# STM32_F4VE.net
KiCad netlist of a schematic drawn in Altium Designer
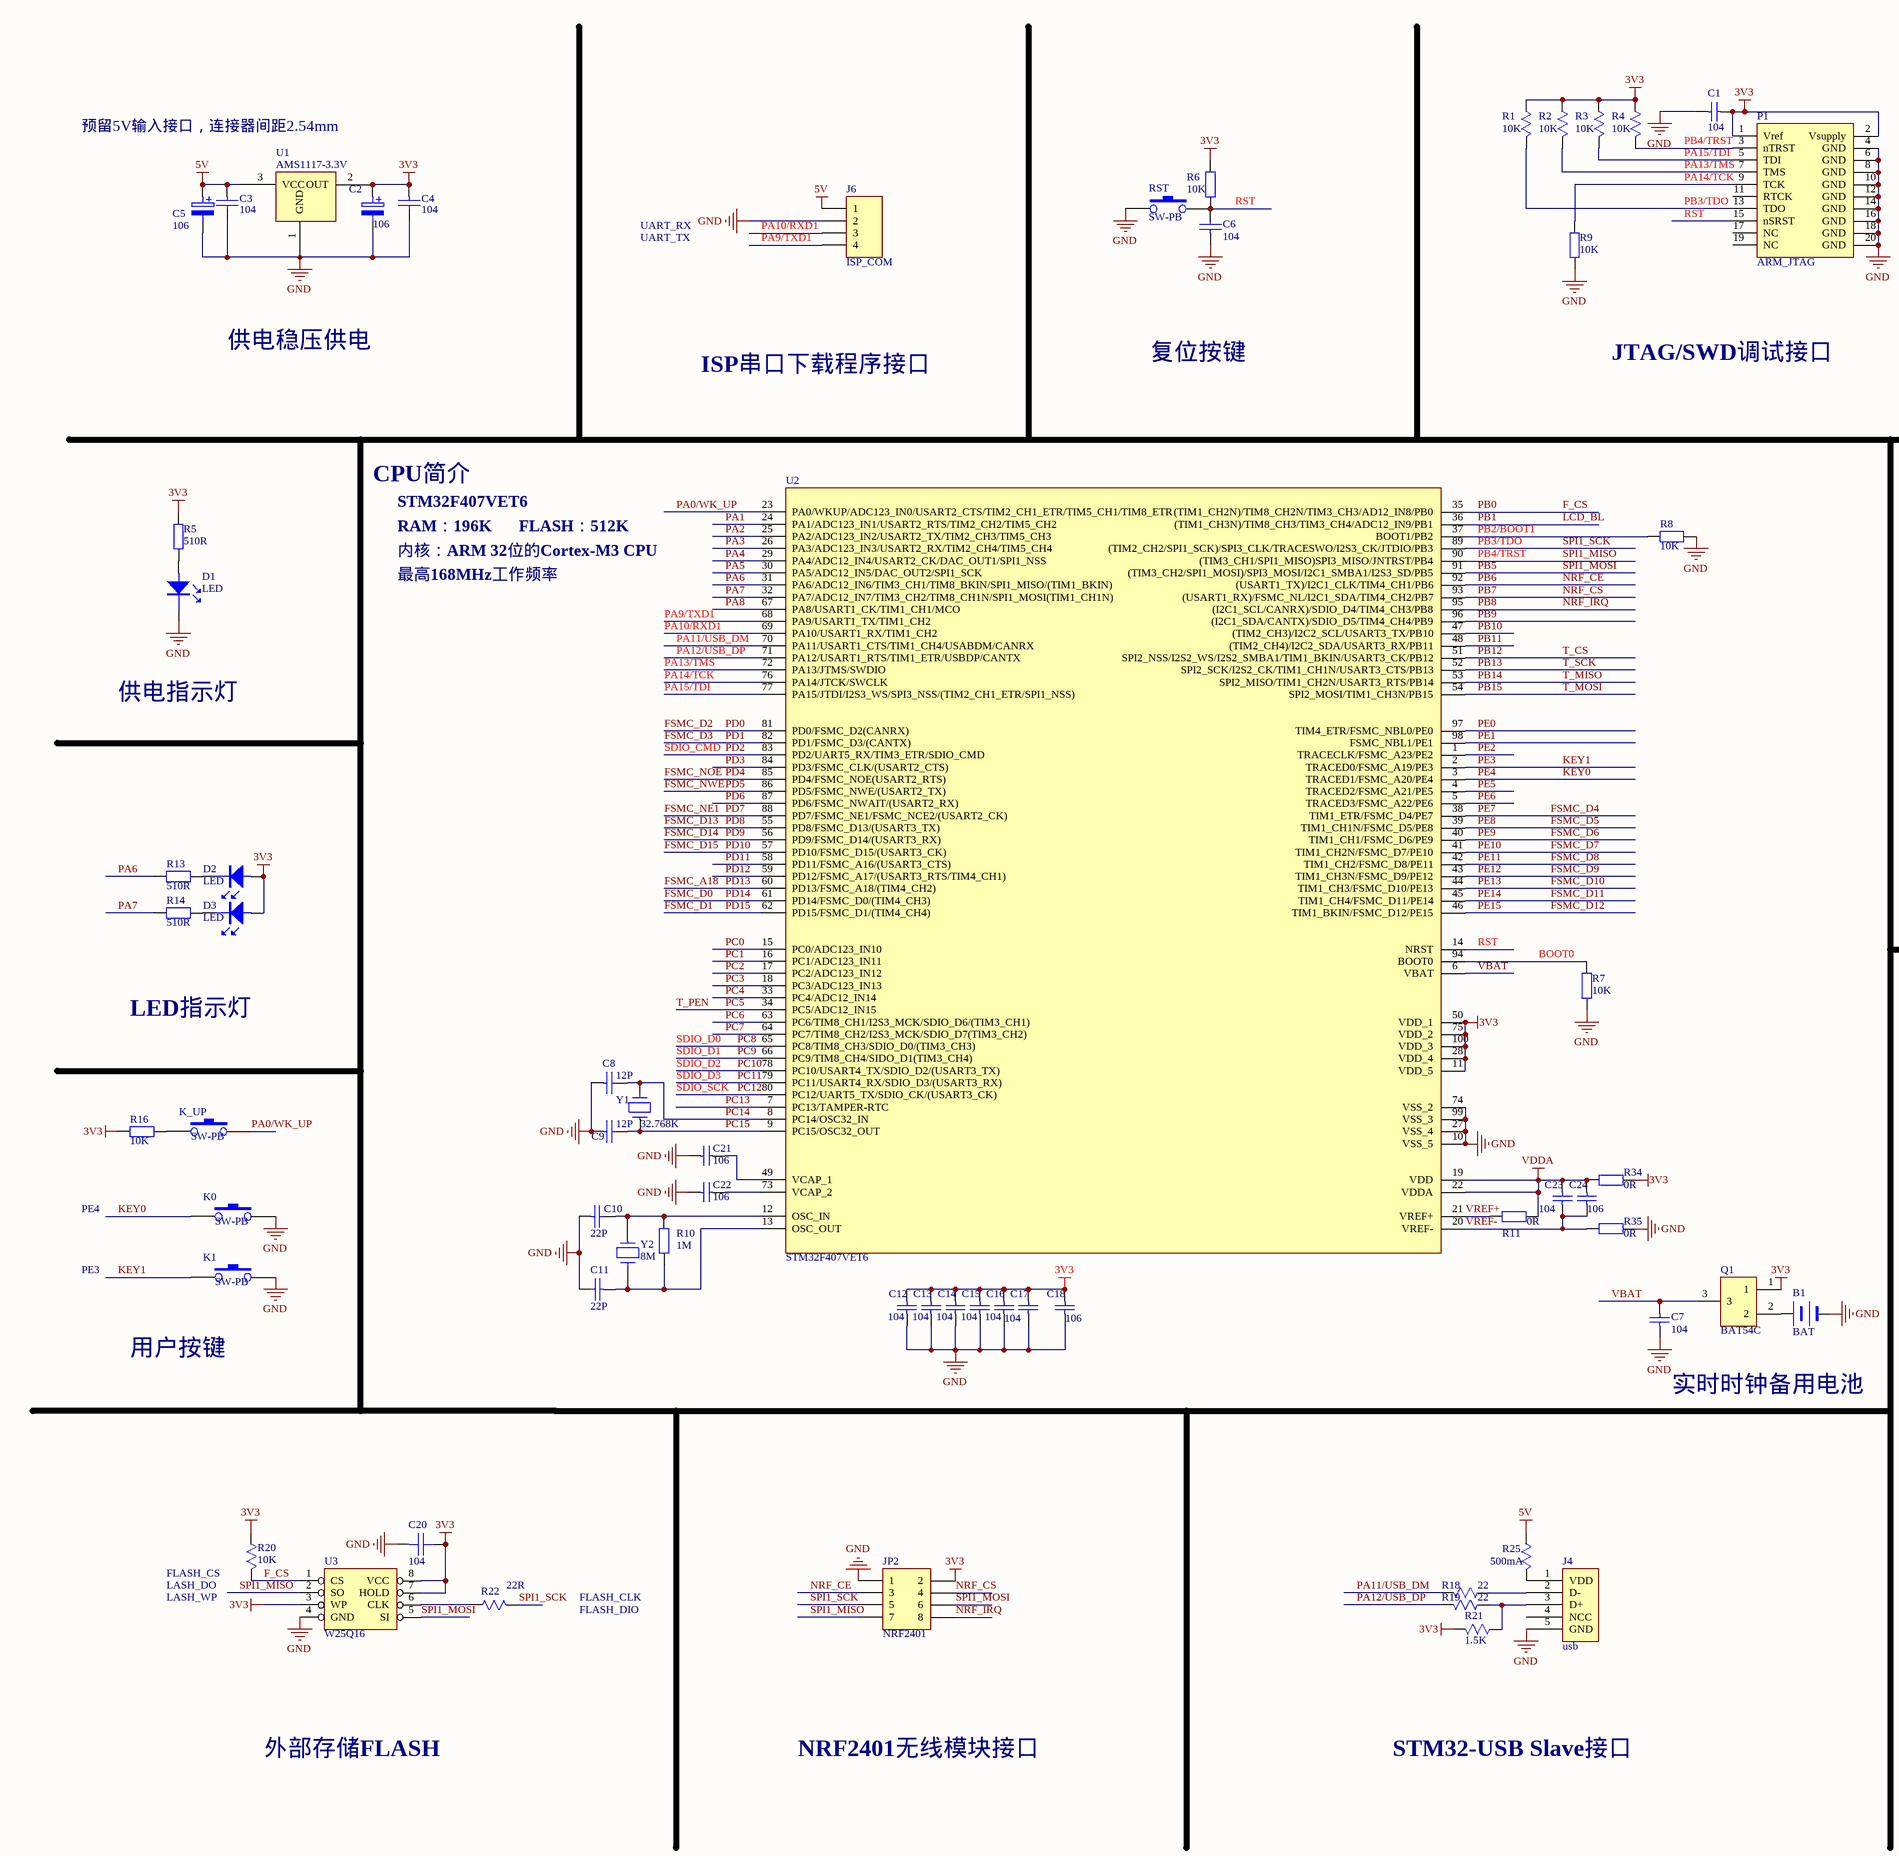
[diagram p0: STM32_F4VE.SchDoc, left]
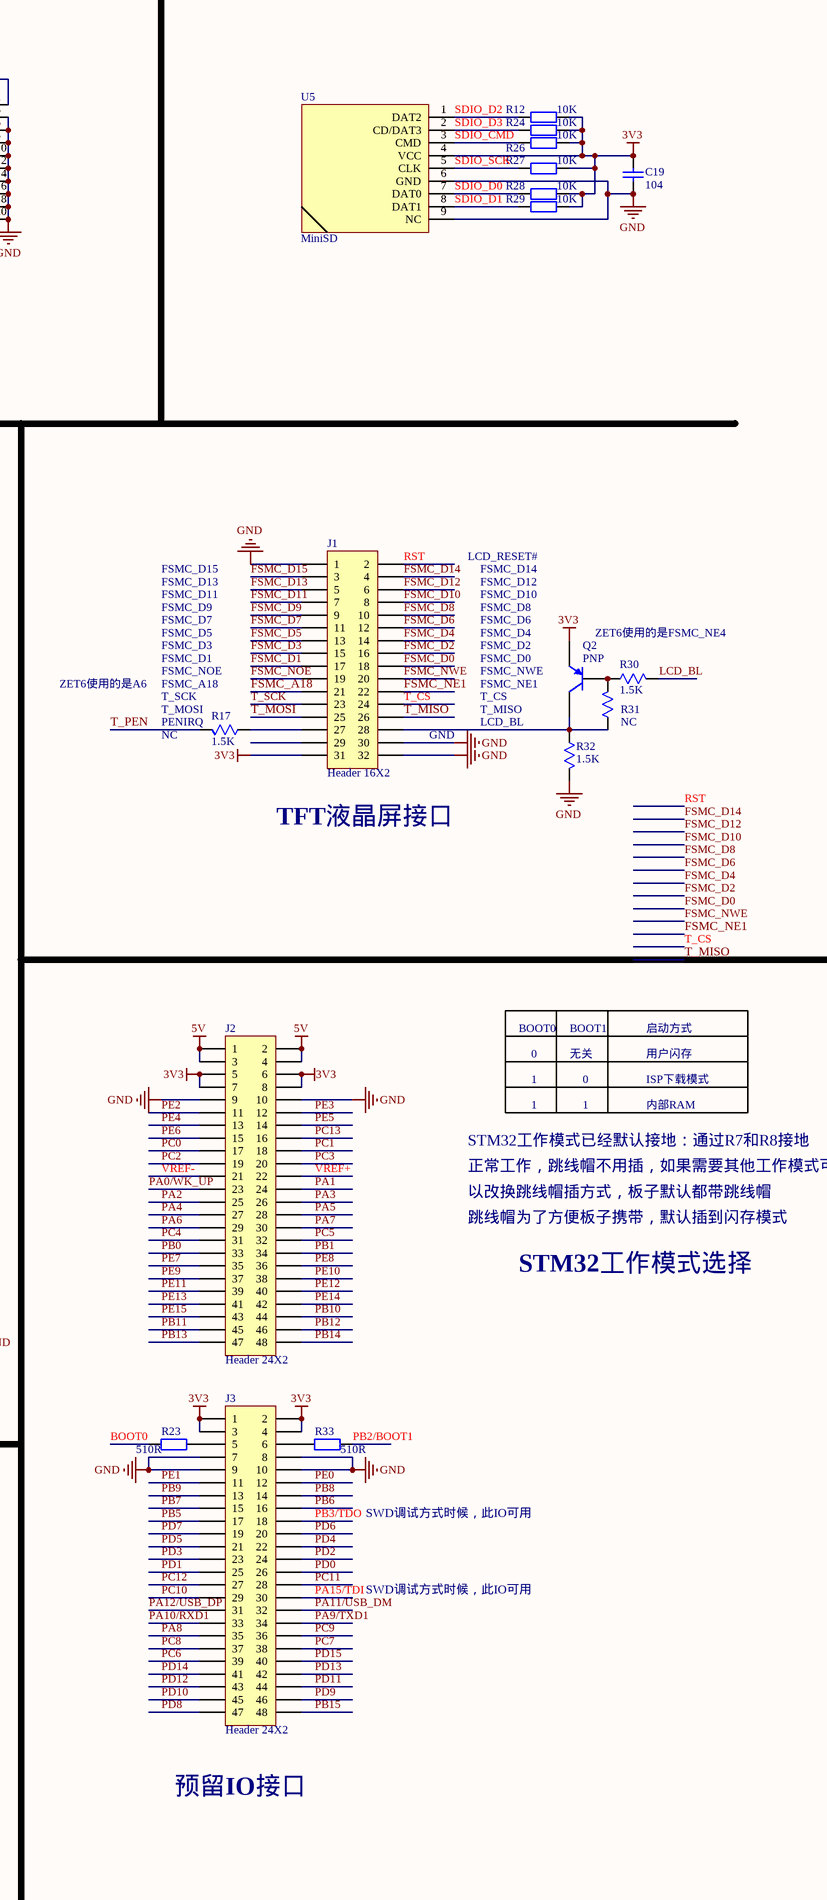
[diagram p1: STM32_F4VE.SchDoc, right]

(export (version "E")
  (design (tool "Eeschema 10.0.6"))
  (components
    (comp (ref "B1") (value "BAT") (footprint "BAT") (libsource (lib "*") (part "BATTERY")))
    (comp (ref "C1")
      (value "104")
      (footprint "RC0603")
      (description "Capacitor")
      (fields (field (name "PUBLISHER") "Altium Limited"))
      (libsource (lib "*") (part "Cap"))
    )
    (comp (ref "C2") (value "106") (footprint "RC0805") (libsource (lib "*") (part "ELECTRO2")))
    (comp (ref "C3")
      (value "104")
      (footprint "RC0603")
      (description "Capacitor")
      (libsource (lib "") (part "CAP_2"))
    )
    (comp (ref "C4")
      (value "104")
      (footprint "RC0603")
      (description "Capacitor")
      (libsource (lib "") (part "CAP_2"))
    )
    (comp (ref "C5") (value "106") (footprint "RC0805") (libsource (lib "*") (part "ELECTRO2")))
    (comp (ref "C6")
      (value "104")
      (footprint "RC0603")
      (description "Capacitor")
      (libsource (lib "*") (part "CAP"))
    )
    (comp (ref "C7")
      (value "104")
      (footprint "RC0603")
      (description "Capacitor")
      (fields (field (name "PUBLISHER") "Altium Limited"))
      (libsource (lib "") (part "Cap_1"))
    )
    (comp (ref "C8") (value "12P") (footprint "RC0603") (libsource (lib "") (part "CAP_1")))
    (comp (ref "C9") (value "12P") (footprint "RC0603") (libsource (lib "") (part "CAP_1")))
    (comp (ref "C10")
      (value "22P")
      (footprint "RC0603")
      (description "Capacitor")
      (libsource (lib "*") (part "CAP"))
    )
    (comp (ref "C11")
      (value "22P")
      (footprint "RC0603")
      (description "Capacitor")
      (libsource (lib "*") (part "CAP"))
    )
    (comp (ref "C12")
      (value "104")
      (footprint "RC0603")
      (description "Capacitor")
      (fields (field (name "PUBLISHER") "Altium Limited"))
      (libsource (lib "*") (part "Cap"))
    )
    (comp (ref "C13")
      (value "104")
      (footprint "RC0603")
      (description "Capacitor")
      (fields (field (name "PUBLISHER") "Altium Limited"))
      (libsource (lib "*") (part "Cap"))
    )
    (comp (ref "C14")
      (value "104")
      (footprint "RC0603")
      (description "Capacitor")
      (fields (field (name "PUBLISHER") "Altium Limited"))
      (libsource (lib "*") (part "Cap"))
    )
    (comp (ref "C15")
      (value "104")
      (footprint "RC0603")
      (description "Capacitor")
      (fields (field (name "PUBLISHER") "Altium Limited"))
      (libsource (lib "*") (part "Cap"))
    )
    (comp (ref "C16")
      (value "104")
      (footprint "RC0603")
      (description "Capacitor")
      (fields (field (name "PUBLISHER") "Altium Limited"))
      (libsource (lib "*") (part "Cap"))
    )
    (comp (ref "C17")
      (value "104")
      (footprint "RC0603")
      (description "Capacitor")
      (fields (field (name "PUBLISHER") "Altium Limited"))
      (libsource (lib "*") (part "Cap"))
    )
    (comp (ref "C18")
      (value "106")
      (footprint "RC0805")
      (description "Capacitor")
      (fields (field (name "PUBLISHER") "Altium Limited"))
      (libsource (lib "*") (part "Cap"))
    )
    (comp (ref "C19")
      (value "104")
      (footprint "RC0603")
      (description "Capacitor (Semiconductor SIM Model)")
      (fields (field (name "PUBLISHER") "Altium Limited"))
      (libsource (lib "*") (part "Cap Semi"))
    )
    (comp (ref "C20") (value "104") (footprint "RC0603") (libsource (lib "YT1_SCH_99SE") (part "CAP")))
    (comp (ref "C21")
      (value "106")
      (footprint "RC0805")
      (description "Capacitor")
      (fields (field (name "PUBLISHER") "Altium Limited"))
      (libsource (lib "*") (part "Cap"))
    )
    (comp (ref "C22")
      (value "106")
      (footprint "RC0805")
      (description "Capacitor")
      (fields (field (name "PUBLISHER") "Altium Limited"))
      (libsource (lib "*") (part "Cap"))
    )
    (comp (ref "C23")
      (value "104")
      (footprint "RC0603")
      (description "Capacitor")
      (fields (field (name "PUBLISHER") "Altium Limited"))
      (libsource (lib "*") (part "Cap"))
    )
    (comp (ref "C24")
      (value "106")
      (footprint "RC0805")
      (description "Capacitor")
      (fields (field (name "PUBLISHER") "Altium Limited"))
      (libsource (lib "*") (part "Cap"))
    )
    (comp (ref "D1") (value "LED") (footprint "LED0805") (libsource (lib "*") (part "LED")))
    (comp (ref "D2") (value "LED") (footprint "LED0805") (libsource (lib "*") (part "LED")))
    (comp (ref "D3") (value "LED") (footprint "LED0805") (libsource (lib "*") (part "LED")))
    (comp (ref "J1")
      (value "Header 16X2")
      (footprint "IDE2X16")
      (description "Header, 16-Pin, Dual row")
      (fields (field (name "PUBLISHER") "Altium Limited"))
      (libsource (lib "Miscellaneous Connectors") (part "Header 16X2"))
    )
    (comp (ref "J2")
      (value "Header 24X2")
      (footprint "IDE2X24")
      (description "Header, 24-Pin, Dual row")
      (fields (field (name "PUBLISHER") "Altium Limited"))
      (libsource (lib "Miscellaneous Connectors") (part "Header 24X2"))
    )
    (comp (ref "J3")
      (value "Header 24X2")
      (footprint "IDE2X24")
      (description "Header, 24-Pin, Dual row")
      (fields (field (name "PUBLISHER") "Altium Limited"))
      (libsource (lib "Miscellaneous Connectors") (part "Header 24X2"))
    )
    (comp (ref "J4") (value "usb") (footprint "Mini_USB") (libsource (lib "YT1_SCH_99SE") (part "usb")))
    (comp (ref "J6")
      (value "ISP_COM")
      (footprint "HDR1X4")
      (description "Header, 4-Pin")
      (fields (field (name "PUBLISHER") "Altium Limited"))
      (libsource (lib "Miscellaneous Connectors") (part "Header 4"))
    )
    (comp (ref "JP2")
      (value "NRF2401")
      (footprint "IDE2X4")
      (description "Header, 4-Pin, Dual row")
      (fields (field (name "PUBLISHER") "Altium Limited"))
      (libsource (lib "Miscellaneous Connectors") (part "Header 4X2"))
    )
    (comp (ref "K0") (value "SW-PB") (footprint "SW-SPST") (libsource (lib "*") (part "SW-PB")))
    (comp (ref "K1") (value "SW-PB") (footprint "SW-SPST") (libsource (lib "*") (part "SW-PB")))
    (comp (ref "K_UP") (value "SW-PB") (footprint "SW-SPST") (libsource (lib "*") (part "SW-PB")))
    (comp (ref "P1")
      (value "ARM_JTAG")
      (footprint "JTAG-20P")
      (description "JTAG")
      (libsource (lib "LXKJSJ") (part "JTAG"))
    )
    (comp (ref "Q1")
      (value "BAT54C")
      (footprint "SOT-23-BAT54C")
      (libsource (lib "Newcapec9263") (part "BAT54C"))
    )
    (comp (ref "Q2")
      (value "PNP")
      (footprint "PNP_SOT23")
      (description "PNP Bipolar Transistor")
      (fields (field (name "PUBLISHER") "Altium Limited"))
      (libsource (lib "Miscellaneous Devices") (part "PNP"))
    )
    (comp (ref "R1") (value "10K") (footprint "RC0603") (libsource (lib "YT1_SCH_99SE") (part "RES")))
    (comp (ref "R2") (value "10K") (footprint "RC0603") (libsource (lib "YT1_SCH_99SE") (part "RES")))
    (comp (ref "R3") (value "10K") (footprint "RC0603") (libsource (lib "YT1_SCH_99SE") (part "RES")))
    (comp (ref "R4") (value "10K") (footprint "RC0603") (libsource (lib "YT1_SCH_99SE") (part "RES")))
    (comp (ref "R5")
      (value "510R")
      (footprint "RC0603")
      (description "Resistor")
      (libsource (lib "") (part "Res2_3"))
    )
    (comp (ref "R6")
      (value "10K")
      (footprint "RC0603")
      (description "Resistor")
      (libsource (lib "") (part "Res2_1"))
    )
    (comp (ref "R7")
      (value "10K")
      (footprint "RC0603")
      (description "Resistor")
      (libsource (lib "") (part "Res2_3"))
    )
    (comp (ref "R8")
      (value "10K")
      (footprint "RC0603")
      (description "Resistor")
      (libsource (lib "") (part "Res2_2"))
    )
    (comp (ref "R9")
      (value "10K")
      (footprint "RC0603")
      (description "Resistor")
      (libsource (lib "") (part "Res2_3"))
    )
    (comp (ref "R10")
      (value "1M")
      (footprint "RC0603")
      (description "Resistor")
      (libsource (lib "") (part "Res2_1"))
    )
    (comp (ref "R11")
      (value "0R")
      (footprint "RC0603")
      (description "Resistor")
      (libsource (lib "Miscellaneous Devices") (part "Res2"))
    )
    (comp (ref "R12")
      (value "10K")
      (footprint "RC0603")
      (description "Resistor")
      (libsource (lib "Miscellaneous Devices") (part "Res2"))
    )
    (comp (ref "R13")
      (value "510R")
      (footprint "RC0603")
      (description "Resistor")
      (libsource (lib "Miscellaneous Devices") (part "Res2"))
    )
    (comp (ref "R14")
      (value "510R")
      (footprint "RC0603")
      (description "Resistor")
      (libsource (lib "Miscellaneous Devices") (part "Res2"))
    )
    (comp (ref "R16")
      (value "10K")
      (footprint "RC0603")
      (description "Resistor")
      (libsource (lib "") (part "Res2_2"))
    )
    (comp (ref "R17") (value "1.5K") (footprint "RC0603") (libsource (lib "YT1_SCH_99SE") (part "RES")))
    (comp (ref "R18") (value "22") (footprint "RC0603") (libsource (lib "YT1_SCH_99SE") (part "RES")))
    (comp (ref "R19") (value "22") (footprint "RC0603") (libsource (lib "YT1_SCH_99SE") (part "RES")))
    (comp (ref "R20") (value "10K") (footprint "RC0603") (libsource (lib "YT1_SCH_99SE") (part "RES")))
    (comp (ref "R21") (value "1.5K") (footprint "RC0603") (libsource (lib "YT1_SCH_99SE") (part "RES")))
    (comp (ref "R22") (value "22R") (footprint "RC0603") (libsource (lib "YT1_SCH_99SE") (part "RES")))
    (comp (ref "R23")
      (value "510R")
      (footprint "RC0603")
      (description "Resistor")
      (libsource (lib "Miscellaneous Devices") (part "Res2"))
    )
    (comp (ref "R24")
      (value "10K")
      (footprint "RC0603")
      (description "Resistor")
      (libsource (lib "Miscellaneous Devices") (part "Res2"))
    )
    (comp (ref "R25") (value "500mA") (footprint "RC0805") (libsource (lib "YT1_SCH_99SE") (part "RES")))
    (comp (ref "R26")
      (value "10K")
      (footprint "RC0603")
      (description "Resistor")
      (libsource (lib "Miscellaneous Devices") (part "Res2"))
    )
    (comp (ref "R27")
      (value "10K")
      (footprint "RC0603")
      (description "Resistor")
      (libsource (lib "Miscellaneous Devices") (part "Res2"))
    )
    (comp (ref "R28")
      (value "10K")
      (footprint "RC0603")
      (description "Resistor")
      (libsource (lib "Miscellaneous Devices") (part "Res2"))
    )
    (comp (ref "R29")
      (value "10K")
      (footprint "RC0603")
      (description "Resistor")
      (libsource (lib "Miscellaneous Devices") (part "Res2"))
    )
    (comp (ref "R30") (value "1.5K") (footprint "RC0603") (libsource (lib "YT1_SCH_99SE") (part "RES")))
    (comp (ref "R31") (value "NC") (footprint "RC0603") (libsource (lib "YT1_SCH_99SE") (part "RES")))
    (comp (ref "R32") (value "1.5K") (footprint "RC0603") (libsource (lib "YT1_SCH_99SE") (part "RES")))
    (comp (ref "R33")
      (value "510R")
      (footprint "RC0603")
      (description "Resistor")
      (libsource (lib "Miscellaneous Devices") (part "Res2"))
    )
    (comp (ref "R34")
      (value "0R")
      (footprint "RC0603")
      (description "Resistor")
      (libsource (lib "Miscellaneous Devices") (part "Res2"))
    )
    (comp (ref "R35")
      (value "0R")
      (footprint "RC0603")
      (description "Resistor")
      (libsource (lib "Miscellaneous Devices") (part "Res2"))
    )
    (comp (ref "RST") (value "SW-PB") (footprint "SW-SPST") (libsource (lib "*") (part "SW-PB")))
    (comp (ref "U1") (value "AMS1117-3.3V") (footprint "SOT-223") (libsource (lib "*") (part "11")))
    (comp (ref "U2") (value "STM32F407VET6") (libsource (lib "STM32_F4VE") (part "STM32F407VET6")))
    (comp (ref "U3") (value "W25Q16") (footprint "SOP8L") (libsource (lib "YT1_SCH_99SE") (part "W25X16")))
    (comp (ref "U5") (value "MiniSD") (footprint "TF_SD") (libsource (lib "STM32_RF") (part "MiniSD")))
    (comp (ref "Y1")
      (value "32.768K")
      (footprint "JZ32768")
      (description "晶振")
      (libsource (lib "*") (part "CRYSTAL"))
    )
    (comp (ref "Y2")
      (value "8M")
      (footprint "49S_SMD")
      (description "Crystal")
      (libsource (lib "") (part "CRYSTAL_1"))
    )
  )
  (nets
    (net (code "1") (name "/BOOT0") (class "Default")
      (node (ref "R23") (pin "1") (pinfunction "1_1") (pintype "passive"))
      (node (ref "R7") (pin "2") (pinfunction "2_2") (pintype "passive"))
      (node (ref "U2") (pin "94") (pinfunction "BOOT0_94") (pintype "passive"))
    )
    (net (code "2") (name "/FSMC_A18") (class "Default")
      (node (ref "J1") (pin "21") (pinfunction "21_21") (pintype "passive"))
      (node (ref "J3") (pin "42") (pinfunction "42_42") (pintype "passive"))
      (node (ref "U2") (pin "60") (pinfunction "PD13/FSMC_A18/(TIM4_CH2)_60") (pintype "passive"))
    )
    (net (code "3") (name "/FSMC_D0") (class "Default")
      (node (ref "J1") (pin "18") (pinfunction "18_18") (pintype "passive"))
      (node (ref "J3") (pin "41") (pinfunction "41_41") (pintype "passive"))
      (node (ref "U2") (pin "61") (pinfunction "PD14/FSMC_D0/(TIM4_CH3)_61") (pintype "passive"))
    )
    (net (code "4") (name "/FSMC_D1") (class "Default")
      (node (ref "J1") (pin "17") (pinfunction "17_17") (pintype "passive"))
      (node (ref "J3") (pin "40") (pinfunction "40_40") (pintype "passive"))
      (node (ref "U2") (pin "62") (pinfunction "PD15/FSMC_D1/(TIM4_CH4)_62") (pintype "passive"))
    )
    (net (code "5") (name "/FSMC_D2") (class "Default")
      (node (ref "J1") (pin "16") (pinfunction "16_16") (pintype "passive"))
      (node (ref "J3") (pin "26") (pinfunction "26_26") (pintype "passive"))
      (node (ref "U2") (pin "81") (pinfunction "PD0/FSMC_D2(CANRX)_81") (pintype "passive"))
    )
    (net (code "6") (name "/FSMC_D3") (class "Default")
      (node (ref "J1") (pin "15") (pinfunction "15_15") (pintype "passive"))
      (node (ref "J3") (pin "25") (pinfunction "25_25") (pintype "passive"))
      (node (ref "U2") (pin "82") (pinfunction "PD1/FSMC_D3/(CANTX)_82") (pintype "passive"))
    )
    (net (code "7") (name "/FSMC_D4") (class "Default")
      (node (ref "J1") (pin "14") (pinfunction "14_14") (pintype "passive"))
      (node (ref "J2") (pin "35") (pinfunction "35_35") (pintype "passive"))
      (node (ref "U2") (pin "38") (pinfunction "TIM1_ETR/FSMC_D4/PE7_38") (pintype "passive"))
    )
    (net (code "8") (name "/FSMC_D5") (class "Default")
      (node (ref "J1") (pin "13") (pinfunction "13_13") (pintype "passive"))
      (node (ref "J2") (pin "36") (pinfunction "36_36") (pintype "passive"))
      (node (ref "U2") (pin "39") (pinfunction "TIM1_CH1N/FSMC_D5/PE8_39") (pintype "passive"))
    )
    (net (code "9") (name "/FSMC_D6") (class "Default")
      (node (ref "J1") (pin "12") (pinfunction "12_12") (pintype "passive"))
      (node (ref "J2") (pin "37") (pinfunction "37_37") (pintype "passive"))
      (node (ref "U2") (pin "40") (pinfunction "TIM1_CH1/FSMC_D6/PE9_40") (pintype "passive"))
    )
    (net (code "10") (name "/FSMC_D7") (class "Default")
      (node (ref "J1") (pin "11") (pinfunction "11_11") (pintype "passive"))
      (node (ref "J2") (pin "38") (pinfunction "38_38") (pintype "passive"))
      (node (ref "U2") (pin "41") (pinfunction "TIM1_CH2N/FSMC_D7/PE10_41") (pintype "passive"))
    )
    (net (code "11") (name "/FSMC_D8") (class "Default")
      (node (ref "J1") (pin "10") (pinfunction "10_10") (pintype "passive"))
      (node (ref "J2") (pin "39") (pinfunction "39_39") (pintype "passive"))
      (node (ref "U2") (pin "42") (pinfunction "TIM1_CH2/FSMC_D8/PE11_42") (pintype "passive"))
    )
    (net (code "12") (name "/FSMC_D9") (class "Default")
      (node (ref "J1") (pin "9") (pinfunction "9_9") (pintype "passive"))
      (node (ref "J2") (pin "40") (pinfunction "40_40") (pintype "passive"))
      (node (ref "U2") (pin "43") (pinfunction "TIM1_CH3N/FSMC_D9/PE12_43") (pintype "passive"))
    )
    (net (code "13") (name "/FSMC_D10") (class "Default")
      (node (ref "J1") (pin "8") (pinfunction "8_8") (pintype "passive"))
      (node (ref "J2") (pin "41") (pinfunction "41_41") (pintype "passive"))
      (node (ref "U2") (pin "44") (pinfunction "TIM1_CH3/FSMC_D10/PE13_44") (pintype "passive"))
    )
    (net (code "14") (name "/FSMC_D11") (class "Default")
      (node (ref "J1") (pin "7") (pinfunction "7_7") (pintype "passive"))
      (node (ref "J2") (pin "42") (pinfunction "42_42") (pintype "passive"))
      (node (ref "U2") (pin "45") (pinfunction "TIM1_CH4/FSMC_D11/PE14_45") (pintype "passive"))
    )
    (net (code "15") (name "/FSMC_D12") (class "Default")
      (node (ref "J1") (pin "6") (pinfunction "6_6") (pintype "passive"))
      (node (ref "J2") (pin "43") (pinfunction "43_43") (pintype "passive"))
      (node (ref "U2") (pin "46") (pinfunction "TIM1_BKIN/FSMC_D12/PE15_46") (pintype "passive"))
    )
    (net (code "16") (name "/FSMC_D13") (class "Default")
      (node (ref "J1") (pin "5") (pinfunction "5_5") (pintype "passive"))
      (node (ref "J3") (pin "47") (pinfunction "47_47") (pintype "passive"))
      (node (ref "U2") (pin "55") (pinfunction "PD8/FSMC_D13/(USART3_TX)_55") (pintype "passive"))
    )
    (net (code "17") (name "/FSMC_D14") (class "Default")
      (node (ref "J1") (pin "4") (pinfunction "4_4") (pintype "passive"))
      (node (ref "J3") (pin "46") (pinfunction "46_46") (pintype "passive"))
      (node (ref "U2") (pin "56") (pinfunction "PD9/FSMC_D14/(USART3_RX)_56") (pintype "passive"))
    )
    (net (code "18") (name "/FSMC_D15") (class "Default")
      (node (ref "J1") (pin "3") (pinfunction "3_3") (pintype "passive"))
      (node (ref "J3") (pin "45") (pinfunction "45_45") (pintype "passive"))
      (node (ref "U2") (pin "57") (pinfunction "PD10/FSMC_D15/(USART3_CK)_57") (pintype "passive"))
    )
    (net (code "19") (name "/FSMC_NE1") (class "Default")
      (node (ref "J1") (pin "22") (pinfunction "22_22") (pintype "passive"))
      (node (ref "J3") (pin "19") (pinfunction "19_19") (pintype "passive"))
      (node (ref "U2") (pin "88") (pinfunction "PD7/FSMC_NE1/FSMC_NCE2/(USART2_CK)_88") (pintype "passive"))
    )
    (net (code "20") (name "/FSMC_NOE") (class "Default")
      (node (ref "J1") (pin "19") (pinfunction "19_19") (pintype "passive"))
      (node (ref "J3") (pin "22") (pinfunction "22_22") (pintype "passive"))
      (node (ref "U2") (pin "85") (pinfunction "PD4/FSMC_NOE(USART2_RTS)_85") (pintype "passive"))
    )
    (net (code "21") (name "/FSMC_NWE") (class "Default")
      (node (ref "J1") (pin "20") (pinfunction "20_20") (pintype "passive"))
      (node (ref "J3") (pin "21") (pinfunction "21_21") (pintype "passive"))
      (node (ref "U2") (pin "86") (pinfunction "PD5/FSMC_NWE/(USART2_TX)_86") (pintype "passive"))
    )
    (net (code "22") (name "/F_CS") (class "Default")
      (node (ref "J2") (pin "33") (pinfunction "33_33") (pintype "passive"))
      (node (ref "R20") (pin "2") (pinfunction "2_2") (pintype "passive"))
      (node (ref "U2") (pin "35") (pinfunction "(TIM1_CH2N)/TIM8_CH2N/TIM3_CH3/AD12_IN8/PB0_35") (pintype "passive"))
      (node (ref "U3") (pin "1") (pinfunction "CS_1") (pintype "passive"))
    )
    (net (code "23") (name "/KEY0") (class "Default")
      (node (ref "J2") (pin "13") (pinfunction "13_13") (pintype "passive"))
      (node (ref "K0") (pin "1") (pinfunction "1_1") (pintype "passive"))
      (node (ref "U2") (pin "3") (pinfunction "TRACED1/FSMC_A20/PE4_3") (pintype "passive"))
    )
    (net (code "24") (name "/KEY1") (class "Default")
      (node (ref "J2") (pin "12") (pinfunction "12_12") (pintype "passive"))
      (node (ref "K1") (pin "1") (pinfunction "1_1") (pintype "passive"))
      (node (ref "U2") (pin "2") (pinfunction "TRACED0/FSMC_A19/PE3_2") (pintype "passive"))
    )
    (net (code "25") (name "/LCD_BL") (class "Default")
      (node (ref "J2") (pin "34") (pinfunction "34_34") (pintype "passive"))
      (node (ref "R30") (pin "2") (pinfunction "2_2") (pintype "passive"))
      (node (ref "U2") (pin "36") (pinfunction "(TIM1_CH3N)/TIM8_CH3/TIM3_CH4/ADC12_IN9/PB1_36") (pintype "passive"))
    )
    (net (code "26") (name "/NRF_CE") (class "Default")
      (node (ref "J3") (pin "16") (pinfunction "16_16") (pintype "passive"))
      (node (ref "JP2") (pin "3") (pinfunction "3_3") (pintype "passive"))
      (node (ref "U2") (pin "92") (pinfunction "(USART1_TX)/I2C1_CLK/TIM4_CH1/PB6_92") (pintype "passive"))
    )
    (net (code "27") (name "/NRF_CS") (class "Default")
      (node (ref "J3") (pin "15") (pinfunction "15_15") (pintype "passive"))
      (node (ref "JP2") (pin "4") (pinfunction "4_4") (pintype "passive"))
      (node (ref "U2") (pin "93") (pinfunction "(USART1_RX)/FSMC_NL/I2C1_SDA/TIM4_CH2/PB7_93") (pintype "passive"))
    )
    (net (code "28") (name "/NRF_IRQ") (class "Default")
      (node (ref "J3") (pin "14") (pinfunction "14_14") (pintype "passive"))
      (node (ref "JP2") (pin "8") (pinfunction "8_8") (pintype "passive"))
      (node (ref "U2") (pin "95") (pinfunction "(I2C1_SCL/CANRX)/SDIO_D4/TIM4_CH3/PB8_95") (pintype "passive"))
    )
    (net (code "29") (name "/PA0{slash}WK_UP") (class "Default")
      (node (ref "J2") (pin "23") (pinfunction "23_23") (pintype "passive"))
      (node (ref "K_UP") (pin "2") (pinfunction "2_2") (pintype "passive"))
      (node (ref "U2") (pin "23") (pinfunction "PA0/WKUP/ADC123_IN0/USART2_CTS/TIM2_CH1_ETR/TIM5_CH1/TIM8_ETR_23") (pintype "passive"))
    )
    (net (code "30") (name "/PA1") (class "Default")
      (node (ref "J2") (pin "24") (pinfunction "24_24") (pintype "passive"))
      (node (ref "U2") (pin "24") (pinfunction "PA1/ADC123_IN1/USART2_RTS/TIM2_CH2/TIM5_CH2_24") (pintype "passive"))
    )
    (net (code "31") (name "/PA2") (class "Default")
      (node (ref "J2") (pin "25") (pinfunction "25_25") (pintype "passive"))
      (node (ref "U2") (pin "25") (pinfunction "PA2/ADC123_IN2/USART2_TX/TIM2_CH3/TIM5_CH3_25") (pintype "passive"))
    )
    (net (code "32") (name "/PA3") (class "Default")
      (node (ref "J2") (pin "26") (pinfunction "26_26") (pintype "passive"))
      (node (ref "U2") (pin "26") (pinfunction "PA3/ADC123_IN3/USART2_RX/TIM2_CH4/TIM5_CH4_26") (pintype "passive"))
    )
    (net (code "33") (name "/PA4") (class "Default")
      (node (ref "J2") (pin "27") (pinfunction "27_27") (pintype "passive"))
      (node (ref "U2") (pin "29") (pinfunction "PA4/ADC12_IN4/USART2_CK/DAC_OUT1/SPI1_NSS_29") (pintype "passive"))
    )
    (net (code "34") (name "/PA5") (class "Default")
      (node (ref "J2") (pin "28") (pinfunction "28_28") (pintype "passive"))
      (node (ref "U2") (pin "30") (pinfunction "PA5/ADC12_IN5/DAC_OUT2/SPI1_SCK_30") (pintype "passive"))
    )
    (net (code "35") (name "/PA6") (class "Default")
      (node (ref "J2") (pin "29") (pinfunction "29_29") (pintype "passive"))
      (node (ref "R13") (pin "1") (pinfunction "1_1") (pintype "passive"))
      (node (ref "U2") (pin "31") (pinfunction "PA6/ADC12_IN6/TIM3_CH1/TIM8_BKIN/SPI1_MISO/(TIM1_BKIN)_31") (pintype "passive"))
    )
    (net (code "36") (name "/PA7") (class "Default")
      (node (ref "J2") (pin "30") (pinfunction "30_30") (pintype "passive"))
      (node (ref "R14") (pin "1") (pinfunction "1_1") (pintype "passive"))
      (node (ref "U2") (pin "32") (pinfunction "PA7/ADC12_IN7/TIM3_CH2/TIM8_CH1N/SPI1_MOSI(TIM1_CH1N)_32") (pintype "passive"))
    )
    (net (code "37") (name "/PA8") (class "Default")
      (node (ref "J3") (pin "35") (pinfunction "35_35") (pintype "passive"))
      (node (ref "U2") (pin "67") (pinfunction "PA8/USART1_CK/TIM1_CH1/MCO_67") (pintype "passive"))
    )
    (net (code "38") (name "/PA9{slash}TXD1") (class "Default")
      (node (ref "J3") (pin "34") (pinfunction "34_34") (pintype "passive"))
      (node (ref "J6") (pin "4") (pinfunction "4_4") (pintype "passive"))
      (node (ref "U2") (pin "68") (pinfunction "PA9/USART1_TX/TIM1_CH2_68") (pintype "passive"))
    )
    (net (code "39") (name "/PA10{slash}RXD1") (class "Default")
      (node (ref "J3") (pin "33") (pinfunction "33_33") (pintype "passive"))
      (node (ref "J6") (pin "3") (pinfunction "3_3") (pintype "passive"))
      (node (ref "U2") (pin "69") (pinfunction "PA10/USART1_RX/TIM1_CH2_69") (pintype "passive"))
    )
    (net (code "40") (name "/PA11{slash}USB_DM") (class "Default")
      (node (ref "J3") (pin "32") (pinfunction "32_32") (pintype "passive"))
      (node (ref "R18") (pin "2") (pinfunction "2_2") (pintype "passive"))
      (node (ref "U2") (pin "70") (pinfunction "PA11/USART1_CTS/TIM1_CH4/USABDM/CANRX_70") (pintype "passive"))
    )
    (net (code "41") (name "/PA12{slash}USB_DP") (class "Default")
      (node (ref "J3") (pin "31") (pinfunction "31_31") (pintype "passive"))
      (node (ref "R19") (pin "2") (pinfunction "2_2") (pintype "passive"))
      (node (ref "U2") (pin "71") (pinfunction "PA12/USART1_RTS/TIM1_ETR/USBDP/CANTX_71") (pintype "passive"))
    )
    (net (code "42") (name "/PA13{slash}TMS") (class "Default")
      (node (ref "P1") (pin "7") (pinfunction "TMS_7") (pintype "passive"))
      (node (ref "R2") (pin "2") (pinfunction "2_2") (pintype "passive"))
      (node (ref "U2") (pin "72") (pinfunction "PA13/JTMS/SWDIO_72") (pintype "passive"))
    )
    (net (code "43") (name "/PA14{slash}TCK") (class "Default")
      (node (ref "P1") (pin "9") (pinfunction "TCK_9") (pintype "passive"))
      (node (ref "R9") (pin "2") (pinfunction "2_2") (pintype "passive"))
      (node (ref "U2") (pin "76") (pinfunction "PA14/JTCK/SWCLK_76") (pintype "passive"))
    )
    (net (code "44") (name "/PA15{slash}TDI") (class "Default")
      (node (ref "J3") (pin "30") (pinfunction "30_30") (pintype "passive"))
      (node (ref "P1") (pin "5") (pinfunction "TDI_5") (pintype "passive"))
      (node (ref "R3") (pin "2") (pinfunction "2_2") (pintype "passive"))
      (node (ref "U2") (pin "77") (pinfunction "PA15/JTDI/I2S3_WS/SPI3_NSS/(TIM2_CH1_ETR/SPI1_NSS)_77") (pintype "passive"))
    )
    (net (code "45") (name "/PB2{slash}BOOT1") (class "Default")
      (node (ref "R33") (pin "2") (pinfunction "2_2") (pintype "passive"))
      (node (ref "R8") (pin "2") (pinfunction "2_2") (pintype "passive"))
      (node (ref "U2") (pin "37") (pinfunction "BOOT1/PB2_37") (pintype "passive"))
    )
    (net (code "46") (name "/PB3{slash}TDO") (class "Default")
      (node (ref "J3") (pin "18") (pinfunction "18_18") (pintype "passive"))
      (node (ref "JP2") (pin "5") (pinfunction "5_5") (pintype "passive"))
      (node (ref "P1") (pin "13") (pinfunction "TDO_13") (pintype "passive"))
      (node (ref "R1") (pin "2") (pinfunction "2_2") (pintype "passive"))
      (node (ref "R22") (pin "2") (pinfunction "2_2") (pintype "passive"))
      (node (ref "U2") (pin "89") (pinfunction "(TIM2_CH2/SPI1_SCK)/SPI3_CLK/TRACESWO/I2S3_CK/JTDIO/PB3_89") (pintype "passive"))
    )
    (net (code "47") (name "/PB4{slash}TRST") (class "Default")
      (node (ref "JP2") (pin "7") (pinfunction "7_7") (pintype "passive"))
      (node (ref "P1") (pin "3") (pinfunction "nTRST_3") (pintype "passive"))
      (node (ref "R4") (pin "2") (pinfunction "2_2") (pintype "passive"))
      (node (ref "U2") (pin "90") (pinfunction "(TIM3_CH1/SPI1_MISO)SPI3_MISO/JNTRST/PB4_90") (pintype "passive"))
      (node (ref "U3") (pin "2") (pinfunction "SO_2") (pintype "passive"))
    )
    (net (code "48") (name "/PB5") (class "Default")
      (node (ref "J3") (pin "17") (pinfunction "17_17") (pintype "passive"))
      (node (ref "JP2") (pin "6") (pinfunction "6_6") (pintype "passive"))
      (node (ref "U2") (pin "91") (pinfunction "(TIM3_CH2/SPI1_MOSI)/SPI3_MOSI/I2C1_SMBA1/I2S3_SD/PB5_91") (pintype "passive"))
      (node (ref "U3") (pin "5") (pinfunction "SI_5") (pintype "passive"))
    )
    (net (code "49") (name "/PB9") (class "Default")
      (node (ref "J3") (pin "13") (pinfunction "13_13") (pintype "passive"))
      (node (ref "U2") (pin "96") (pinfunction "(I2C1_SDA/CANTX)/SDIO_D5/TIM4_CH4/PB9_96") (pintype "passive"))
    )
    (net (code "50") (name "/PB10") (class "Default")
      (node (ref "J2") (pin "44") (pinfunction "44_44") (pintype "passive"))
      (node (ref "U2") (pin "47") (pinfunction "(TIM2_CH3)/I2C2_SCL/USART3_TX/PB10_47") (pintype "passive"))
    )
    (net (code "51") (name "/PB11") (class "Default")
      (node (ref "J2") (pin "45") (pinfunction "45_45") (pintype "passive"))
      (node (ref "U2") (pin "48") (pinfunction "(TIM2_CH4)/I2C2_SDA/USART3_RX/PB11_48") (pintype "passive"))
    )
    (net (code "52") (name "/PB12") (class "Default")
      (node (ref "J1") (pin "24") (pinfunction "24_24") (pintype "passive"))
      (node (ref "J2") (pin "46") (pinfunction "46_46") (pintype "passive"))
      (node (ref "U2") (pin "51") (pinfunction "SPI2_NSS/I2S2_WS/I2S2_SMBA1/TIM1_BKIN/USART3_CK/PB12_51") (pintype "passive"))
    )
    (net (code "53") (name "/PB13") (class "Default")
      (node (ref "J1") (pin "23") (pinfunction "23_23") (pintype "passive"))
      (node (ref "J2") (pin "47") (pinfunction "47_47") (pintype "passive"))
      (node (ref "U2") (pin "52") (pinfunction "SPI2_SCK/I2S2_CK/TIM1_CH1N/USART3_CTS/PB13_52") (pintype "passive"))
    )
    (net (code "54") (name "/PB14") (class "Default")
      (node (ref "J1") (pin "26") (pinfunction "26_26") (pintype "passive"))
      (node (ref "J2") (pin "48") (pinfunction "48_48") (pintype "passive"))
      (node (ref "U2") (pin "53") (pinfunction "SPI2_MISO/TIM1_CH2N/USART3_RTS/PB14_53") (pintype "passive"))
    )
    (net (code "55") (name "/PB15") (class "Default")
      (node (ref "J1") (pin "25") (pinfunction "25_25") (pintype "passive"))
      (node (ref "J3") (pin "48") (pinfunction "48_48") (pintype "passive"))
      (node (ref "U2") (pin "54") (pinfunction "SPI2_MOSI/TIM1_CH3N/PB15_54") (pintype "passive"))
    )
    (net (code "56") (name "/PC0") (class "Default")
      (node (ref "J2") (pin "17") (pinfunction "17_17") (pintype "passive"))
      (node (ref "U2") (pin "15") (pinfunction "PC0/ADC123_IN10_15") (pintype "passive"))
    )
    (net (code "57") (name "/PC1") (class "Default")
      (node (ref "J2") (pin "18") (pinfunction "18_18") (pintype "passive"))
      (node (ref "U2") (pin "16") (pinfunction "PC1/ADC123_IN11_16") (pintype "passive"))
    )
    (net (code "58") (name "/PC2") (class "Default")
      (node (ref "J2") (pin "19") (pinfunction "19_19") (pintype "passive"))
      (node (ref "U2") (pin "17") (pinfunction "PC2/ADC123_IN12_17") (pintype "passive"))
    )
    (net (code "59") (name "/PC3") (class "Default")
      (node (ref "J2") (pin "20") (pinfunction "20_20") (pintype "passive"))
      (node (ref "U2") (pin "18") (pinfunction "PC3/ADC123_IN13_18") (pintype "passive"))
    )
    (net (code "60") (name "/PC4") (class "Default")
      (node (ref "J2") (pin "31") (pinfunction "31_31") (pintype "passive"))
      (node (ref "U2") (pin "33") (pinfunction "PC4/ADC12_IN14_33") (pintype "passive"))
    )
    (net (code "61") (name "/PC5") (class "Default")
      (node (ref "J2") (pin "32") (pinfunction "32_32") (pintype "passive"))
      (node (ref "R17") (pin "2") (pinfunction "2_2") (pintype "passive"))
      (node (ref "U2") (pin "34") (pinfunction "PC5/ADC12_IN15_34") (pintype "passive"))
    )
    (net (code "62") (name "/PC6") (class "Default")
      (node (ref "J3") (pin "39") (pinfunction "39_39") (pintype "passive"))
      (node (ref "U2") (pin "63") (pinfunction "PC6/TIM8_CH1/I2S3_MCK/SDIO_D6/(TIM3_CH1)_63") (pintype "passive"))
    )
    (net (code "63") (name "/PC7") (class "Default")
      (node (ref "J3") (pin "38") (pinfunction "38_38") (pintype "passive"))
      (node (ref "U2") (pin "64") (pinfunction "PC7/TIM8_CH2/I2S3_MCK/SDIO_D7(TIM3_CH2)_64") (pintype "passive"))
    )
    (net (code "64") (name "/PC8") (class "Default")
      (node (ref "J3") (pin "37") (pinfunction "37_37") (pintype "passive"))
      (node (ref "R28") (pin "1") (pinfunction "1_1") (pintype "passive"))
      (node (ref "U2") (pin "65") (pinfunction "PC8/TIM8_CH3/SDIO_D0/(TIM3_CH3)_65") (pintype "passive"))
      (node (ref "U5") (pin "7") (pinfunction "DAT0_7") (pintype "passive"))
    )
    (net (code "65") (name "/PC9") (class "Default")
      (node (ref "J3") (pin "36") (pinfunction "36_36") (pintype "passive"))
      (node (ref "R29") (pin "1") (pinfunction "1_1") (pintype "passive"))
      (node (ref "U2") (pin "66") (pinfunction "PC9/TIM8_CH4/SIDO_D1(TIM3_CH4)_66") (pintype "passive"))
      (node (ref "U5") (pin "8") (pinfunction "DAT1_8") (pintype "passive"))
    )
    (net (code "66") (name "/PC10") (class "Default")
      (node (ref "J3") (pin "29") (pinfunction "29_29") (pintype "passive"))
      (node (ref "R12") (pin "1") (pinfunction "1_1") (pintype "passive"))
      (node (ref "U2") (pin "78") (pinfunction "PC10/USART4_TX/SDIO_D2/(USART3_TX)_78") (pintype "passive"))
      (node (ref "U5") (pin "1") (pinfunction "DAT2_1") (pintype "passive"))
    )
    (net (code "67") (name "/PC11") (class "Default")
      (node (ref "J3") (pin "28") (pinfunction "28_28") (pintype "passive"))
      (node (ref "R24") (pin "1") (pinfunction "1_1") (pintype "passive"))
      (node (ref "U2") (pin "79") (pinfunction "PC11/USART4_RX/SDIO_D3/(USART3_RX)_79") (pintype "passive"))
      (node (ref "U5") (pin "2") (pinfunction "CD/DAT3_2") (pintype "passive"))
    )
    (net (code "68") (name "/PC12") (class "Default")
      (node (ref "J3") (pin "27") (pinfunction "27_27") (pintype "passive"))
      (node (ref "R27") (pin "1") (pinfunction "1_1") (pintype "passive"))
      (node (ref "U2") (pin "80") (pinfunction "PC12/UART5_TX/SDIO_CK/(USART3_CK)_80") (pintype "passive"))
      (node (ref "U5") (pin "5") (pinfunction "CLK_5") (pintype "passive"))
    )
    (net (code "69") (name "/PC13") (class "Default")
      (node (ref "J2") (pin "16") (pinfunction "16_16") (pintype "passive"))
      (node (ref "U2") (pin "7") (pinfunction "PC13/TAMPER-RTC_7") (pintype "passive"))
    )
    (net (code "70") (name "/PC14") (class "Default")
      (node (ref "C8") (pin "2") (pintype "passive"))
      (node (ref "U2") (pin "8") (pinfunction "PC14/OSC32_IN_8") (pintype "passive"))
      (node (ref "Y1") (pin "2") (pintype "passive"))
    )
    (net (code "71") (name "/PC15") (class "Default")
      (node (ref "C9") (pin "2") (pintype "passive"))
      (node (ref "U2") (pin "9") (pinfunction "PC15/OSC32_OUT_9") (pintype "passive"))
      (node (ref "Y1") (pin "1") (pintype "passive"))
    )
    (net (code "72") (name "/PD2") (class "Default")
      (node (ref "J3") (pin "24") (pinfunction "24_24") (pintype "passive"))
      (node (ref "R26") (pin "1") (pinfunction "1_1") (pintype "passive"))
      (node (ref "U2") (pin "83") (pinfunction "PD2/UART5_RX/TIM3_ETR/SDIO_CMD_83") (pintype "passive"))
      (node (ref "U5") (pin "3") (pinfunction "CMD_3") (pintype "passive"))
    )
    (net (code "73") (name "/PD3") (class "Default")
      (node (ref "J3") (pin "23") (pinfunction "23_23") (pintype "passive"))
      (node (ref "U2") (pin "84") (pinfunction "PD3/FSMC_CLK/(USART2_CTS)_84") (pintype "passive"))
    )
    (net (code "74") (name "/PD6") (class "Default")
      (node (ref "J3") (pin "20") (pinfunction "20_20") (pintype "passive"))
      (node (ref "U2") (pin "87") (pinfunction "PD6/FSMC_NWAIT/(USART2_RX)_87") (pintype "passive"))
    )
    (net (code "75") (name "/PD11") (class "Default")
      (node (ref "J3") (pin "44") (pinfunction "44_44") (pintype "passive"))
      (node (ref "U2") (pin "58") (pinfunction "PD11/FSMC_A16/(USART3_CTS)_58") (pintype "passive"))
    )
    (net (code "76") (name "/PD12") (class "Default")
      (node (ref "J3") (pin "43") (pinfunction "43_43") (pintype "passive"))
      (node (ref "U2") (pin "59") (pinfunction "PD12/FSMC_A17/(USART3_RTS/TIM4_CH1)_59") (pintype "passive"))
    )
    (net (code "77") (name "/PE0") (class "Default")
      (node (ref "J3") (pin "12") (pinfunction "12_12") (pintype "passive"))
      (node (ref "U2") (pin "97") (pinfunction "TIM4_ETR/FSMC_NBL0/PE0_97") (pintype "passive"))
    )
    (net (code "78") (name "/PE1") (class "Default")
      (node (ref "J3") (pin "11") (pinfunction "11_11") (pintype "passive"))
      (node (ref "U2") (pin "98") (pinfunction "FSMC_NBL1/PE1_98") (pintype "passive"))
    )
    (net (code "79") (name "/PE2") (class "Default")
      (node (ref "J2") (pin "11") (pinfunction "11_11") (pintype "passive"))
      (node (ref "U2") (pin "1") (pinfunction "TRACECLK/FSMC_A23/PE2_1") (pintype "passive"))
    )
    (net (code "80") (name "/PE5") (class "Default")
      (node (ref "J2") (pin "14") (pinfunction "14_14") (pintype "passive"))
      (node (ref "U2") (pin "4") (pinfunction "TRACED2/FSMC_A21/PE5_4") (pintype "passive"))
    )
    (net (code "81") (name "/PE6") (class "Default")
      (node (ref "J2") (pin "15") (pinfunction "15_15") (pintype "passive"))
      (node (ref "U2") (pin "5") (pinfunction "TRACED3/FSMC_A22/PE6_5") (pintype "passive"))
    )
    (net (code "82") (name "/RST") (class "Default")
      (node (ref "C6") (pin "2") (pinfunction "2_2") (pintype "passive"))
      (node (ref "J1") (pin "2") (pinfunction "2_2") (pintype "passive"))
      (node (ref "P1") (pin "15") (pinfunction "nSRST_15") (pintype "passive"))
      (node (ref "R6") (pin "2") (pinfunction "2_2") (pintype "passive"))
      (node (ref "RST") (pin "2") (pinfunction "2_2") (pintype "passive"))
      (node (ref "U2") (pin "14") (pinfunction "NRST_14") (pintype "passive"))
    )
    (net (code "83") (name "/VBAT") (class "Default")
      (node (ref "C7") (pin "2") (pinfunction "2_2") (pintype "passive"))
      (node (ref "Q1") (pin "3") (pinfunction "3_3") (pintype "passive"))
      (node (ref "U2") (pin "6") (pinfunction "VBAT_6") (pintype "passive"))
    )
    (net (code "84") (name "/VREF+") (class "Default")
      (node (ref "J2") (pin "22") (pinfunction "22_22") (pintype "passive"))
      (node (ref "R11") (pin "1") (pinfunction "1_1") (pintype "passive"))
      (node (ref "U2") (pin "21") (pinfunction "VREF+_21") (pintype "passive"))
    )
    (net (code "85") (name "/VREF-") (class "Default")
      (node (ref "C23") (pin "2") (pinfunction "2_2") (pintype "passive"))
      (node (ref "C24") (pin "2") (pinfunction "2_2") (pintype "passive"))
      (node (ref "J2") (pin "21") (pinfunction "21_21") (pintype "passive"))
      (node (ref "R35") (pin "1") (pinfunction "1_1") (pintype "passive"))
      (node (ref "U2") (pin "20") (pinfunction "VREF-_20") (pintype "passive"))
    )
    (net (code "86") (name "3V3") (class "Default")
      (node (ref "C1") (pin "2") (pinfunction "2_2") (pintype "passive"))
      (node (ref "C12") (pin "1") (pinfunction "1_1") (pintype "passive"))
      (node (ref "C13") (pin "1") (pinfunction "1_1") (pintype "passive"))
      (node (ref "C14") (pin "1") (pinfunction "1_1") (pintype "passive"))
      (node (ref "C15") (pin "1") (pinfunction "1_1") (pintype "passive"))
      (node (ref "C16") (pin "1") (pinfunction "1_1") (pintype "passive"))
      (node (ref "C17") (pin "1") (pinfunction "1_1") (pintype "passive"))
      (node (ref "C18") (pin "1") (pinfunction "1_1") (pintype "passive"))
      (node (ref "C19") (pin "1") (pinfunction "1_1") (pintype "passive"))
      (node (ref "C2") (pin "1") (pintype "passive"))
      (node (ref "C20") (pin "2") (pinfunction "2_2") (pintype "passive"))
      (node (ref "C4") (pin "1") (pinfunction "1_1") (pintype "passive"))
      (node (ref "D2") (pin "1") (pinfunction "1_1") (pintype "passive"))
      (node (ref "D3") (pin "1") (pinfunction "1_1") (pintype "passive"))
      (node (ref "J1") (pin "31") (pinfunction "31_31") (pintype "passive"))
      (node (ref "J2") (pin "5") (pinfunction "5_5") (pintype "passive"))
      (node (ref "J2") (pin "6") (pinfunction "6_6") (pintype "passive"))
      (node (ref "J2") (pin "7") (pinfunction "7_7") (pintype "passive"))
      (node (ref "J2") (pin "8") (pinfunction "8_8") (pintype "passive"))
      (node (ref "J3") (pin "1") (pinfunction "1_1") (pintype "passive"))
      (node (ref "J3") (pin "2") (pinfunction "2_2") (pintype "passive"))
      (node (ref "J3") (pin "3") (pinfunction "3_3") (pintype "passive"))
      (node (ref "J3") (pin "4") (pinfunction "4_4") (pintype "passive"))
      (node (ref "JP2") (pin "2") (pinfunction "2_2") (pintype "passive"))
      (node (ref "P1") (pin "1") (pinfunction "Vref_1") (pintype "passive"))
      (node (ref "P1") (pin "2") (pinfunction "Vsupply_2") (pintype "passive"))
      (node (ref "Q1") (pin "1") (pinfunction "1_1") (pintype "passive"))
      (node (ref "Q2") (pin "2") (pinfunction "E_2") (pintype "passive"))
      (node (ref "R1") (pin "1") (pinfunction "1_1") (pintype "passive"))
      (node (ref "R12") (pin "2") (pinfunction "2_2") (pintype "passive"))
      (node (ref "R16") (pin "2") (pinfunction "2_2") (pintype "passive"))
      (node (ref "R2") (pin "1") (pinfunction "1_1") (pintype "passive"))
      (node (ref "R20") (pin "1") (pinfunction "1_1") (pintype "passive"))
      (node (ref "R21") (pin "2") (pinfunction "2_2") (pintype "passive"))
      (node (ref "R24") (pin "2") (pinfunction "2_2") (pintype "passive"))
      (node (ref "R26") (pin "2") (pinfunction "2_2") (pintype "passive"))
      (node (ref "R27") (pin "2") (pinfunction "2_2") (pintype "passive"))
      (node (ref "R28") (pin "2") (pinfunction "2_2") (pintype "passive"))
      (node (ref "R29") (pin "2") (pinfunction "2_2") (pintype "passive"))
      (node (ref "R3") (pin "1") (pinfunction "1_1") (pintype "passive"))
      (node (ref "R34") (pin "2") (pinfunction "2_2") (pintype "passive"))
      (node (ref "R4") (pin "1") (pinfunction "1_1") (pintype "passive"))
      (node (ref "R5") (pin "2") (pinfunction "2_2") (pintype "passive"))
      (node (ref "R6") (pin "1") (pinfunction "1_1") (pintype "passive"))
      (node (ref "U1") (pin "2") (pinfunction "OUT_2") (pintype "passive"))
      (node (ref "U2") (pin "100") (pinfunction "VDD_3_100") (pintype "passive"))
      (node (ref "U2") (pin "11") (pinfunction "VDD_5_11") (pintype "passive"))
      (node (ref "U2") (pin "28") (pinfunction "VDD_4_28") (pintype "passive"))
      (node (ref "U2") (pin "50") (pinfunction "VDD_1_50") (pintype "passive"))
      (node (ref "U2") (pin "75") (pinfunction "VDD_2_75") (pintype "passive"))
      (node (ref "U3") (pin "3") (pinfunction "WP_3") (pintype "passive"))
      (node (ref "U3") (pin "7") (pinfunction "HOLD_7") (pintype "passive"))
      (node (ref "U3") (pin "8") (pinfunction "VCC_8") (pintype "passive"))
      (node (ref "U5") (pin "4") (pinfunction "VCC_4") (pintype "passive"))
    )
    (net (code "87") (name "5V") (class "Default")
      (node (ref "C3") (pin "1") (pinfunction "1_1") (pintype "passive"))
      (node (ref "C5") (pin "1") (pintype "passive"))
      (node (ref "J2") (pin "1") (pinfunction "1_1") (pintype "passive"))
      (node (ref "J2") (pin "2") (pinfunction "2_2") (pintype "passive"))
      (node (ref "J2") (pin "3") (pinfunction "3_3") (pintype "passive"))
      (node (ref "J2") (pin "4") (pinfunction "4_4") (pintype "passive"))
      (node (ref "J6") (pin "1") (pinfunction "1_1") (pintype "passive"))
      (node (ref "R25") (pin "1") (pinfunction "1_1") (pintype "passive"))
      (node (ref "U1") (pin "3") (pinfunction "VCC_3") (pintype "passive"))
    )
    (net (code "88") (name "GND") (class "Default")
      (node (ref "B1") (pin "2") (pintype "passive"))
      (node (ref "C1") (pin "1") (pinfunction "1_1") (pintype "passive"))
      (node (ref "C10") (pin "1") (pinfunction "1_1") (pintype "passive"))
      (node (ref "C11") (pin "2") (pinfunction "2_2") (pintype "passive"))
      (node (ref "C12") (pin "2") (pinfunction "2_2") (pintype "passive"))
      (node (ref "C13") (pin "2") (pinfunction "2_2") (pintype "passive"))
      (node (ref "C14") (pin "2") (pinfunction "2_2") (pintype "passive"))
      (node (ref "C15") (pin "2") (pinfunction "2_2") (pintype "passive"))
      (node (ref "C16") (pin "2") (pinfunction "2_2") (pintype "passive"))
      (node (ref "C17") (pin "2") (pinfunction "2_2") (pintype "passive"))
      (node (ref "C18") (pin "2") (pinfunction "2_2") (pintype "passive"))
      (node (ref "C19") (pin "2") (pinfunction "2_2") (pintype "passive"))
      (node (ref "C2") (pin "2") (pintype "passive"))
      (node (ref "C20") (pin "1") (pinfunction "1_1") (pintype "passive"))
      (node (ref "C21") (pin "1") (pinfunction "1_1") (pintype "passive"))
      (node (ref "C22") (pin "1") (pinfunction "1_1") (pintype "passive"))
      (node (ref "C3") (pin "2") (pinfunction "2_2") (pintype "passive"))
      (node (ref "C4") (pin "2") (pinfunction "2_2") (pintype "passive"))
      (node (ref "C5") (pin "2") (pintype "passive"))
      (node (ref "C6") (pin "1") (pinfunction "1_1") (pintype "passive"))
      (node (ref "C7") (pin "1") (pinfunction "1_1") (pintype "passive"))
      (node (ref "C8") (pin "1") (pintype "passive"))
      (node (ref "C9") (pin "1") (pintype "passive"))
      (node (ref "D1") (pin "2") (pinfunction "2_2") (pintype "passive"))
      (node (ref "J1") (pin "1") (pinfunction "1_1") (pintype "passive"))
      (node (ref "J1") (pin "30") (pinfunction "30_30") (pintype "passive"))
      (node (ref "J1") (pin "32") (pinfunction "32_32") (pintype "passive"))
      (node (ref "J2") (pin "10") (pinfunction "10_10") (pintype "passive"))
      (node (ref "J2") (pin "9") (pinfunction "9_9") (pintype "passive"))
      (node (ref "J3") (pin "10") (pinfunction "10_10") (pintype "passive"))
      (node (ref "J3") (pin "7") (pinfunction "7_7") (pintype "passive"))
      (node (ref "J3") (pin "8") (pinfunction "8_8") (pintype "passive"))
      (node (ref "J3") (pin "9") (pinfunction "9_9") (pintype "passive"))
      (node (ref "J4") (pin "5") (pinfunction "GND_5") (pintype "passive"))
      (node (ref "J6") (pin "2") (pinfunction "2_2") (pintype "passive"))
      (node (ref "JP2") (pin "1") (pinfunction "1_1") (pintype "passive"))
      (node (ref "K0") (pin "2") (pinfunction "2_2") (pintype "passive"))
      (node (ref "K1") (pin "2") (pinfunction "2_2") (pintype "passive"))
      (node (ref "P1") (pin "10") (pinfunction "GND_10") (pintype "passive"))
      (node (ref "P1") (pin "12") (pinfunction "GND_12") (pintype "passive"))
      (node (ref "P1") (pin "14") (pinfunction "GND_14") (pintype "passive"))
      (node (ref "P1") (pin "16") (pinfunction "GND_16") (pintype "passive"))
      (node (ref "P1") (pin "18") (pinfunction "GND_18") (pintype "passive"))
      (node (ref "P1") (pin "20") (pinfunction "GND_20") (pintype "passive"))
      (node (ref "P1") (pin "4") (pinfunction "GND_4") (pintype "passive"))
      (node (ref "P1") (pin "6") (pinfunction "GND_6") (pintype "passive"))
      (node (ref "P1") (pin "8") (pinfunction "GND_8") (pintype "passive"))
      (node (ref "R32") (pin "2") (pinfunction "2_2") (pintype "passive"))
      (node (ref "R35") (pin "2") (pinfunction "2_2") (pintype "passive"))
      (node (ref "R7") (pin "1") (pinfunction "1_1") (pintype "passive"))
      (node (ref "R8") (pin "1") (pinfunction "1_1") (pintype "passive"))
      (node (ref "R9") (pin "1") (pinfunction "1_1") (pintype "passive"))
      (node (ref "RST") (pin "1") (pinfunction "1_1") (pintype "passive"))
      (node (ref "U1") (pin "1") (pinfunction "GND_1") (pintype "passive"))
      (node (ref "U2") (pin "10") (pinfunction "VSS_5_10") (pintype "passive"))
      (node (ref "U2") (pin "27") (pinfunction "VSS_4_27") (pintype "passive"))
      (node (ref "U2") (pin "74") (pinfunction "VSS_2_74") (pintype "passive"))
      (node (ref "U2") (pin "99") (pinfunction "VSS_3_99") (pintype "passive"))
      (node (ref "U3") (pin "4") (pinfunction "GND_4") (pintype "passive"))
      (node (ref "U5") (pin "6") (pinfunction "GND_6") (pintype "passive"))
      (node (ref "U5") (pin "9") (pinfunction "NC_9") (pintype "passive"))
    )
    (net (code "89") (name "Net-(B1-Pad1)") (class "Default")
      (node (ref "B1") (pin "1") (pintype "passive"))
      (node (ref "Q1") (pin "2") (pinfunction "2_2") (pintype "passive"))
    )
    (net (code "90") (name "Net-(D1-Pad1)") (class "Default")
      (node (ref "D1") (pin "1") (pinfunction "1_1") (pintype "passive"))
      (node (ref "R5") (pin "1") (pinfunction "1_1") (pintype "passive"))
    )
    (net (code "91") (name "Net-(D2-Pad2)") (class "Default")
      (node (ref "D2") (pin "2") (pinfunction "2_2") (pintype "passive"))
      (node (ref "R13") (pin "2") (pinfunction "2_2") (pintype "passive"))
    )
    (net (code "92") (name "Net-(D3-Pad2)") (class "Default")
      (node (ref "D3") (pin "2") (pinfunction "2_2") (pintype "passive"))
      (node (ref "R14") (pin "2") (pinfunction "2_2") (pintype "passive"))
    )
    (net (code "93") (name "Net-(J1-Pad27)") (class "Default")
      (node (ref "J1") (pin "27") (pinfunction "27_27") (pintype "passive"))
      (node (ref "R17") (pin "1") (pinfunction "1_1") (pintype "passive"))
    )
    (net (code "94") (name "Net-(J3-Pad5)") (class "Default")
      (node (ref "J3") (pin "5") (pinfunction "5_5") (pintype "passive"))
      (node (ref "R23") (pin "2") (pinfunction "2_2") (pintype "passive"))
    )
    (net (code "95") (name "Net-(J3-Pad6)") (class "Default")
      (node (ref "J3") (pin "6") (pinfunction "6_6") (pintype "passive"))
      (node (ref "R33") (pin "1") (pinfunction "1_1") (pintype "passive"))
    )
    (net (code "96") (name "Net-(J4-D+)") (class "Default")
      (node (ref "J4") (pin "3") (pinfunction "D+_3") (pintype "passive"))
      (node (ref "R19") (pin "1") (pinfunction "1_1") (pintype "passive"))
      (node (ref "R21") (pin "1") (pinfunction "1_1") (pintype "passive"))
    )
    (net (code "97") (name "Net-(J4-D-)") (class "Default")
      (node (ref "J4") (pin "2") (pinfunction "D-_2") (pintype "passive"))
      (node (ref "R18") (pin "1") (pinfunction "1_1") (pintype "passive"))
    )
    (net (code "98") (name "Net-(J4-VDD)") (class "Default")
      (node (ref "J4") (pin "1") (pinfunction "VDD_1") (pintype "passive"))
      (node (ref "R25") (pin "2") (pinfunction "2_2") (pintype "passive"))
    )
    (net (code "99") (name "Net-(K_UP-Pad1)") (class "Default")
      (node (ref "K_UP") (pin "1") (pinfunction "1_1") (pintype "passive"))
      (node (ref "R16") (pin "1") (pinfunction "1_1") (pintype "passive"))
    )
    (net (code "100") (name "Net-(Q2-B)") (class "Default")
      (node (ref "Q2") (pin "1") (pinfunction "B_1") (pintype "passive"))
      (node (ref "R30") (pin "1") (pinfunction "1_1") (pintype "passive"))
      (node (ref "R31") (pin "2") (pinfunction "2_2") (pintype "passive"))
    )
    (net (code "101") (name "Net-(Q2-C)") (class "Default")
      (node (ref "J1") (pin "28") (pinfunction "28_28") (pintype "passive"))
      (node (ref "Q2") (pin "3") (pinfunction "C_3") (pintype "passive"))
      (node (ref "R31") (pin "1") (pinfunction "1_1") (pintype "passive"))
      (node (ref "R32") (pin "1") (pinfunction "1_1") (pintype "passive"))
    )
    (net (code "102") (name "Net-(U2-OSC_IN)") (class "Default")
      (node (ref "C10") (pin "2") (pinfunction "2_2") (pintype "passive"))
      (node (ref "R10") (pin "1") (pinfunction "1_1") (pintype "passive"))
      (node (ref "U2") (pin "12") (pinfunction "OSC_IN_12") (pintype "passive"))
      (node (ref "Y2") (pin "1") (pinfunction "1_1") (pintype "passive"))
    )
    (net (code "103") (name "Net-(U2-OSC_OUT)") (class "Default")
      (node (ref "C11") (pin "1") (pinfunction "1_1") (pintype "passive"))
      (node (ref "R10") (pin "2") (pinfunction "2_2") (pintype "passive"))
      (node (ref "U2") (pin "13") (pinfunction "OSC_OUT_13") (pintype "passive"))
      (node (ref "Y2") (pin "2") (pinfunction "2_2") (pintype "passive"))
    )
    (net (code "104") (name "Net-(U2-VCAP_1)") (class "Default")
      (node (ref "C21") (pin "2") (pinfunction "2_2") (pintype "passive"))
      (node (ref "U2") (pin "49") (pinfunction "VCAP_1_49") (pintype "passive"))
    )
    (net (code "105") (name "Net-(U2-VCAP_2)") (class "Default")
      (node (ref "C22") (pin "2") (pinfunction "2_2") (pintype "passive"))
      (node (ref "U2") (pin "73") (pinfunction "VCAP_2_73") (pintype "passive"))
    )
    (net (code "106") (name "Net-(U3-CLK)") (class "Default")
      (node (ref "R22") (pin "1") (pinfunction "1_1") (pintype "passive"))
      (node (ref "U3") (pin "6") (pinfunction "CLK_6") (pintype "passive"))
    )
    (net (code "107") (name "VDDA") (class "Default")
      (node (ref "C23") (pin "1") (pinfunction "1_1") (pintype "passive"))
      (node (ref "C24") (pin "1") (pinfunction "1_1") (pintype "passive"))
      (node (ref "R11") (pin "2") (pinfunction "2_2") (pintype "passive"))
      (node (ref "R34") (pin "1") (pinfunction "1_1") (pintype "passive"))
      (node (ref "U2") (pin "19") (pinfunction "VDD_19") (pintype "passive"))
      (node (ref "U2") (pin "22") (pinfunction "VDDA_22") (pintype "passive"))
    )
    (net (code "108") (name "unconnected-(J1-Pad29)") (class "Default")
      (node (ref "J1") (pin "29") (pinfunction "29_29") (pintype "passive"))
    )
    (net (code "109") (name "unconnected-(J4-NCC-Pad4)") (class "Default")
      (node (ref "J4") (pin "4") (pinfunction "NCC_4") (pintype "passive"))
    )
    (net (code "110") (name "unconnected-(P1-NC-Pad17)") (class "Default")
      (node (ref "P1") (pin "17") (pinfunction "NC_17") (pintype "passive"))
    )
    (net (code "111") (name "unconnected-(P1-NC-Pad19)") (class "Default")
      (node (ref "P1") (pin "19") (pinfunction "NC_19") (pintype "passive"))
    )
    (net (code "112") (name "unconnected-(P1-RTCK-Pad11)") (class "Default")
      (node (ref "P1") (pin "11") (pinfunction "RTCK_11") (pintype "passive"))
    )
  )
)
